# FPGA_Power_SPI.net
KiCad netlist of a schematic drawn in Altium Designer
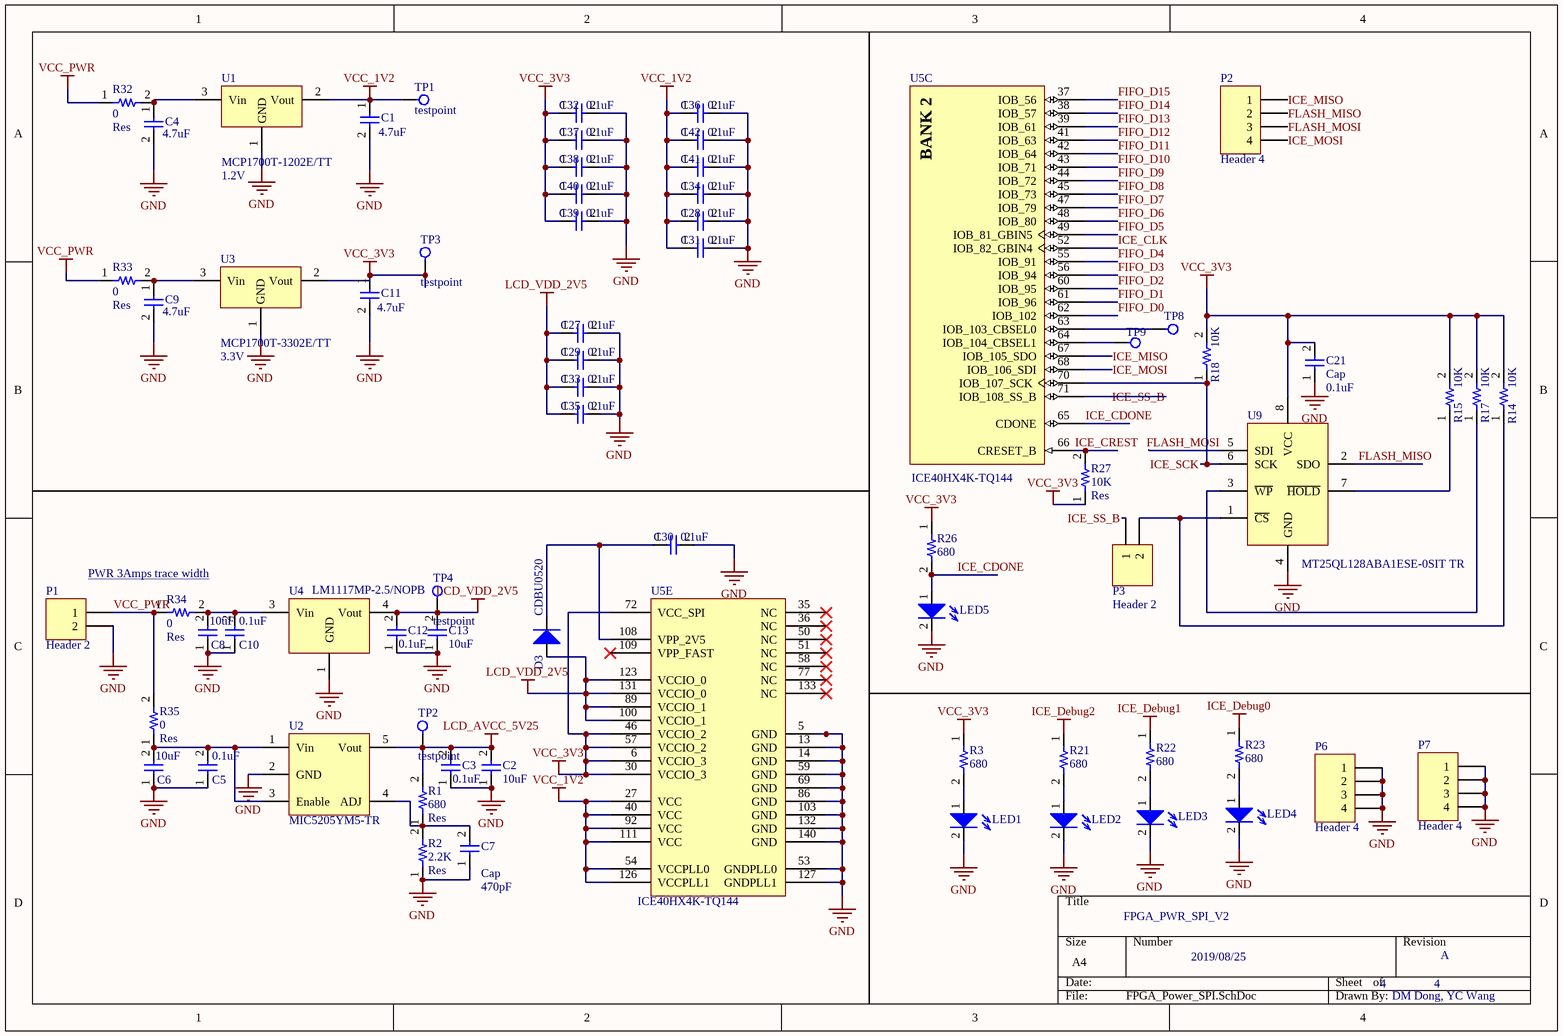
[diagram p0: FPGA_Power_SPI.SchDoc]

(export (version "E")
  (design (tool "Eeschema 10.0.6"))
  (components
    (comp (ref "C1")
      (value "4.7uF")
      (footprint "Cap_4.7uF")
      (description "Multilayer Ceramic Capacitors MLCC - SMD/SMT 6.3V 4.7uF 0603 X5R 10%")
      (fields (field (name "Comment") "C0603C475K9PAC7411") (field (name "CREATED BY") "Daoming Dong"))
      (libsource (lib "USB_FPGA_SLM_v1") (part "Cap_4.7uF"))
    )
    (comp (ref "C2")
      (value "10uF")
      (footprint "Cap_10uF")
      (description "Multilayer Ceramic Capacitors MLCC - SMD/SMT 0603 6.3V 10uF X5R 10% Soft Term")
      (fields (field (name "Comment") "C1608X5R0J106K080AE") (field (name "CREATED BY") "Daoming Dong"))
      (libsource (lib "USB_FPGA_SLM_v1") (part "Cap_10uF"))
    )
    (comp (ref "C3")
      (value "0.1uF")
      (footprint "Cap_0.1uF")
      (description "Multilayer Ceramic Capacitors MLCC - SMD/SMT 0.1uF 10% 50V AEC-Q200")
      (fields (field (name "Comment") "AC0603KRX7R9BB104") (field (name "CREATED BY") "Daoming Dong"))
      (libsource (lib "USB_FPGA_SLM_v1") (part "Cap_0.1uF"))
    )
    (comp (ref "C4")
      (value "4.7uF")
      (footprint "Cap_4.7uF")
      (description "Multilayer Ceramic Capacitors MLCC - SMD/SMT 6.3V 4.7uF 0603 X5R 10%")
      (fields (field (name "Comment") "C0603C475K9PAC7411") (field (name "CREATED BY") "Daoming Dong"))
      (libsource (lib "USB_FPGA_SLM_v1") (part "Cap_4.7uF"))
    )
    (comp (ref "C5")
      (value "0.1uF")
      (footprint "Cap_0.1uF")
      (description "Multilayer Ceramic Capacitors MLCC - SMD/SMT 0.1uF 10% 50V AEC-Q200")
      (fields (field (name "Comment") "AC0603KRX7R9BB104") (field (name "CREATED BY") "Daoming Dong"))
      (libsource (lib "USB_FPGA_SLM_v1") (part "Cap_0.1uF"))
    )
    (comp (ref "C6")
      (value "10uF")
      (footprint "Cap_10uF")
      (description "Multilayer Ceramic Capacitors MLCC - SMD/SMT 0603 6.3V 10uF X5R 10% Soft Term")
      (fields (field (name "Comment") "C1608X5R0J106K080AE") (field (name "CREATED BY") "Daoming Dong"))
      (libsource (lib "USB_FPGA_SLM_v1") (part "Cap_10uF"))
    )
    (comp (ref "C7")
      (value "470pF")
      (footprint "CAP_470pF")
      (description "Multilayer Ceramic Capacitors MLCC - SMD/SMT 25V 470pF X7R 0402 10% AEC-Q200")
      (fields
        (field (name "COMPONENT NAME") "Cap")
        (field (name "Comment") "C0402S471K3RACAUTO")
        (field (name "CREATED BY") "Daoming Dong")
      )
      (libsource (lib "USB_FPGA_SLM_v1") (part "Cap_470pF"))
    )
    (comp (ref "C8")
      (value "10uF")
      (footprint "Cap_10uF")
      (description "Multilayer Ceramic Capacitors MLCC - SMD/SMT 0603 6.3V 10uF X5R 10% Soft Term")
      (fields (field (name "Comment") "C1608X5R0J106K080AE") (field (name "CREATED BY") "Daoming Dong"))
      (libsource (lib "USB_FPGA_SLM_v1") (part "Cap_10uF"))
    )
    (comp (ref "C9")
      (value "4.7uF")
      (footprint "Cap_4.7uF")
      (description "Multilayer Ceramic Capacitors MLCC - SMD/SMT 6.3V 4.7uF 0603 X5R 10%")
      (fields (field (name "Comment") "C0603C475K9PAC7411") (field (name "CREATED BY") "Daoming Dong"))
      (libsource (lib "USB_FPGA_SLM_v1") (part "Cap_4.7uF"))
    )
    (comp (ref "C10")
      (value "0.1uF")
      (footprint "Cap_0.1uF")
      (description "Multilayer Ceramic Capacitors MLCC - SMD/SMT 0.1uF 10% 50V AEC-Q200")
      (fields (field (name "Comment") "AC0603KRX7R9BB104") (field (name "CREATED BY") "Daoming Dong"))
      (libsource (lib "USB_FPGA_SLM_v1") (part "Cap_0.1uF"))
    )
    (comp (ref "C11")
      (value "4.7uF")
      (footprint "Cap_4.7uF")
      (description "Multilayer Ceramic Capacitors MLCC - SMD/SMT 6.3V 4.7uF 0603 X5R 10%")
      (fields (field (name "Comment") "C0603C475K9PAC7411") (field (name "CREATED BY") "Daoming Dong"))
      (libsource (lib "USB_FPGA_SLM_v1") (part "Cap_4.7uF"))
    )
    (comp (ref "C12")
      (value "0.1uF")
      (footprint "Cap_0.1uF")
      (description "Multilayer Ceramic Capacitors MLCC - SMD/SMT 0.1uF 10% 50V AEC-Q200")
      (fields (field (name "Comment") "AC0603KRX7R9BB104") (field (name "CREATED BY") "Daoming Dong"))
      (libsource (lib "USB_FPGA_SLM_v1") (part "Cap_0.1uF"))
    )
    (comp (ref "C13")
      (value "10uF")
      (footprint "Cap_10uF")
      (description "Multilayer Ceramic Capacitors MLCC - SMD/SMT 0603 6.3V 10uF X5R 10% Soft Term")
      (fields (field (name "Comment") "C1608X5R0J106K080AE") (field (name "CREATED BY") "Daoming Dong"))
      (libsource (lib "USB_FPGA_SLM_v1") (part "Cap_10uF"))
    )
    (comp (ref "C21")
      (value "0.1uF")
      (footprint "Cap_0.1uF")
      (description "Multilayer Ceramic Capacitors MLCC - SMD/SMT 0.1uF 10% 50V AEC-Q200")
      (fields
        (field (name "COMPONENT NAME") "Cap")
        (field (name "Comment") "AC0603KRX7R9BB104")
        (field (name "CREATED BY") "Daoming Dong")
      )
      (libsource (lib "USB_FPGA_SLM_v1") (part "Cap_0.1uF"))
    )
    (comp (ref "C27")
      (value "0.1uF")
      (footprint "Cap_0.1uF")
      (description "Multilayer Ceramic Capacitors MLCC - SMD/SMT 0.1uF 10% 50V AEC-Q200")
      (fields (field (name "Comment") "AC0603KRX7R9BB104") (field (name "CREATED BY") "Daoming Dong"))
      (libsource (lib "USB_FPGA_SLM_v1") (part "Cap_0.1uF"))
    )
    (comp (ref "C28")
      (value "0.1uF")
      (footprint "Cap_0.1uF")
      (description "Multilayer Ceramic Capacitors MLCC - SMD/SMT 0.1uF 10% 50V AEC-Q200")
      (fields (field (name "Comment") "AC0603KRX7R9BB104") (field (name "CREATED BY") "Daoming Dong"))
      (libsource (lib "USB_FPGA_SLM_v1") (part "Cap_0.1uF"))
    )
    (comp (ref "C29")
      (value "0.1uF")
      (footprint "Cap_0.1uF")
      (description "Multilayer Ceramic Capacitors MLCC - SMD/SMT 0.1uF 10% 50V AEC-Q200")
      (fields (field (name "Comment") "AC0603KRX7R9BB104") (field (name "CREATED BY") "Daoming Dong"))
      (libsource (lib "USB_FPGA_SLM_v1") (part "Cap_0.1uF"))
    )
    (comp (ref "C30")
      (value "0.1uF")
      (footprint "Cap_0.1uF")
      (description "Multilayer Ceramic Capacitors MLCC - SMD/SMT 0.1uF 10% 50V AEC-Q200")
      (fields (field (name "Comment") "AC0603KRX7R9BB104") (field (name "CREATED BY") "Daoming Dong"))
      (libsource (lib "USB_FPGA_SLM_v1") (part "Cap_0.1uF"))
    )
    (comp (ref "C31")
      (value "0.1uF")
      (footprint "Cap_0.1uF")
      (description "Multilayer Ceramic Capacitors MLCC - SMD/SMT 0.1uF 10% 50V AEC-Q200")
      (fields (field (name "Comment") "AC0603KRX7R9BB104") (field (name "CREATED BY") "Daoming Dong"))
      (libsource (lib "USB_FPGA_SLM_v1") (part "Cap_0.1uF"))
    )
    (comp (ref "C32")
      (value "0.1uF")
      (footprint "Cap_0.1uF")
      (description "Multilayer Ceramic Capacitors MLCC - SMD/SMT 0.1uF 10% 50V AEC-Q200")
      (fields (field (name "Comment") "AC0603KRX7R9BB104") (field (name "CREATED BY") "Daoming Dong"))
      (libsource (lib "USB_FPGA_SLM_v1") (part "Cap_0.1uF"))
    )
    (comp (ref "C33")
      (value "0.1uF")
      (footprint "Cap_0.1uF")
      (description "Multilayer Ceramic Capacitors MLCC - SMD/SMT 0.1uF 10% 50V AEC-Q200")
      (fields (field (name "Comment") "AC0603KRX7R9BB104") (field (name "CREATED BY") "Daoming Dong"))
      (libsource (lib "USB_FPGA_SLM_v1") (part "Cap_0.1uF"))
    )
    (comp (ref "C34")
      (value "0.1uF")
      (footprint "Cap_0.1uF")
      (description "Multilayer Ceramic Capacitors MLCC - SMD/SMT 0.1uF 10% 50V AEC-Q200")
      (fields (field (name "Comment") "AC0603KRX7R9BB104") (field (name "CREATED BY") "Daoming Dong"))
      (libsource (lib "USB_FPGA_SLM_v1") (part "Cap_0.1uF"))
    )
    (comp (ref "C35")
      (value "0.1uF")
      (footprint "Cap_0.1uF")
      (description "Multilayer Ceramic Capacitors MLCC - SMD/SMT 0.1uF 10% 50V AEC-Q200")
      (fields (field (name "Comment") "AC0603KRX7R9BB104") (field (name "CREATED BY") "Daoming Dong"))
      (libsource (lib "USB_FPGA_SLM_v1") (part "Cap_0.1uF"))
    )
    (comp (ref "C36")
      (value "0.1uF")
      (footprint "Cap_0.1uF")
      (description "Multilayer Ceramic Capacitors MLCC - SMD/SMT 0.1uF 10% 50V AEC-Q200")
      (fields (field (name "Comment") "AC0603KRX7R9BB104") (field (name "CREATED BY") "Daoming Dong"))
      (libsource (lib "USB_FPGA_SLM_v1") (part "Cap_0.1uF"))
    )
    (comp (ref "C37")
      (value "0.1uF")
      (footprint "Cap_0.1uF")
      (description "Multilayer Ceramic Capacitors MLCC - SMD/SMT 0.1uF 10% 50V AEC-Q200")
      (fields (field (name "Comment") "AC0603KRX7R9BB104") (field (name "CREATED BY") "Daoming Dong"))
      (libsource (lib "USB_FPGA_SLM_v1") (part "Cap_0.1uF"))
    )
    (comp (ref "C38")
      (value "0.1uF")
      (footprint "Cap_0.1uF")
      (description "Multilayer Ceramic Capacitors MLCC - SMD/SMT 0.1uF 10% 50V AEC-Q200")
      (fields (field (name "Comment") "AC0603KRX7R9BB104") (field (name "CREATED BY") "Daoming Dong"))
      (libsource (lib "USB_FPGA_SLM_v1") (part "Cap_0.1uF"))
    )
    (comp (ref "C39")
      (value "0.1uF")
      (footprint "Cap_0.1uF")
      (description "Multilayer Ceramic Capacitors MLCC - SMD/SMT 0.1uF 10% 50V AEC-Q200")
      (fields (field (name "Comment") "AC0603KRX7R9BB104") (field (name "CREATED BY") "Daoming Dong"))
      (libsource (lib "USB_FPGA_SLM_v1") (part "Cap_0.1uF"))
    )
    (comp (ref "C40")
      (value "0.1uF")
      (footprint "Cap_0.1uF")
      (description "Multilayer Ceramic Capacitors MLCC - SMD/SMT 0.1uF 10% 50V AEC-Q200")
      (fields (field (name "Comment") "AC0603KRX7R9BB104") (field (name "CREATED BY") "Daoming Dong"))
      (libsource (lib "USB_FPGA_SLM_v1") (part "Cap_0.1uF"))
    )
    (comp (ref "C41")
      (value "0.1uF")
      (footprint "Cap_0.1uF")
      (description "Multilayer Ceramic Capacitors MLCC - SMD/SMT 0.1uF 10% 50V AEC-Q200")
      (fields (field (name "Comment") "AC0603KRX7R9BB104") (field (name "CREATED BY") "Daoming Dong"))
      (libsource (lib "USB_FPGA_SLM_v1") (part "Cap_0.1uF"))
    )
    (comp (ref "C42")
      (value "0.1uF")
      (footprint "Cap_0.1uF")
      (description "Multilayer Ceramic Capacitors MLCC - SMD/SMT 0.1uF 10% 50V AEC-Q200")
      (fields (field (name "Comment") "AC0603KRX7R9BB104") (field (name "CREATED BY") "Daoming Dong"))
      (libsource (lib "USB_FPGA_SLM_v1") (part "Cap_0.1uF"))
    )
    (comp (ref "D3")
      (value "CDBU0520")
      (footprint "SchottkyDiode_CDBU0520")
      (description "Schottky Diodes & Rectifiers VR=20V, IO=500mA")
      (fields (field (name "CREATED BY") "Daoming Dong"))
      (libsource (lib "USB_FPGA_SLM_v1") (part "SDiode_CDBU0520"))
    )
    (comp (ref "LED1")
      (value "TLMS1000-GS08")
      (footprint "LED_RED")
      (description "Standard LEDs - SMD RED")
      (fields (field (name "CREATED BY") "Daoming Dong"))
      (libsource (lib "USB_FPGA_SLM_v1") (part "LED_RED"))
    )
    (comp (ref "LED2")
      (value "TLMS1000-GS08")
      (footprint "LED_RED")
      (description "Standard LEDs - SMD RED")
      (fields (field (name "CREATED BY") "Daoming Dong"))
      (libsource (lib "USB_FPGA_SLM_v1") (part "LED_RED"))
    )
    (comp (ref "LED3")
      (value "TLMS1000-GS08")
      (footprint "LED_RED")
      (description "Standard LEDs - SMD RED")
      (fields (field (name "CREATED BY") "Daoming Dong"))
      (libsource (lib "USB_FPGA_SLM_v1") (part "LED_RED"))
    )
    (comp (ref "LED4")
      (value "TLMS1000-GS08")
      (footprint "LED_RED")
      (description "Standard LEDs - SMD RED")
      (fields (field (name "CREATED BY") "Daoming Dong"))
      (libsource (lib "USB_FPGA_SLM_v1") (part "LED_RED"))
    )
    (comp (ref "LED5")
      (value "TLMS1000-GS08")
      (footprint "LED_RED")
      (description "Standard LEDs - SMD RED")
      (fields (field (name "CREATED BY") "Daoming Dong"))
      (libsource (lib "USB_FPGA_SLM_v1") (part "LED_RED"))
    )
    (comp (ref "P1")
      (value "Header 2")
      (footprint "HDR1X2")
      (description "Header, 2-Pin")
      (fields (field (name "PUBLISHER") "Altium Limited"))
      (libsource (lib "") (part "Header 2_1"))
    )
    (comp (ref "P2")
      (value "Header 4")
      (footprint "HDR2X2")
      (description "Header, 4-Pin")
      (fields (field (name "PUBLISHER") "Altium Limited"))
      (libsource (lib "Miscellaneous Connectors") (part "Header 4"))
    )
    (comp (ref "P3")
      (value "Header 2")
      (footprint "HDR1X2")
      (description "Header, 2-Pin")
      (fields (field (name "PUBLISHER") "Altium Limited"))
      (libsource (lib "Miscellaneous Connectors") (part "Header 2"))
    )
    (comp (ref "P6")
      (value "Header 4")
      (footprint "HDR2X2")
      (description "Header, 4-Pin")
      (fields (field (name "PUBLISHER") "Altium Limited"))
      (libsource (lib "Miscellaneous Connectors") (part "Header 4"))
    )
    (comp (ref "P7")
      (value "Header 4")
      (footprint "HDR2X2")
      (description "Header, 4-Pin")
      (fields (field (name "PUBLISHER") "Altium Limited"))
      (libsource (lib "Miscellaneous Connectors") (part "Header 4"))
    )
    (comp (ref "R1")
      (value "680")
      (footprint "RES_680")
      (description "Thin Film Resistors - SMD 680 ohm 1% 50 ppm Thin Film")
      (fields
        (field (name "COMPONENT NAME") "Res")
        (field (name "Comment") "RT0603FRE13680RL")
        (field (name "CREATED BY") "Daoming Dong")
      )
      (libsource (lib "USB_FPGA_SLM_v1") (part "Res_680"))
    )
    (comp (ref "R2")
      (value "2.2K")
      (footprint "RES_2.2K")
      (description "Thick Film Resistors - SMD 1/10Watt 2.2Kohms 5% Commercial Use")
      (fields
        (field (name "COMPONENT NAME") "Res")
        (field (name "Comment") "CRCW06032K20JNEAC")
        (field (name "CREATED BY") "Daoming Dong")
      )
      (libsource (lib "USB_FPGA_SLM_v1") (part "Res_2.2K"))
    )
    (comp (ref "R3")
      (value "680")
      (footprint "RES_680")
      (description "Thin Film Resistors - SMD 680 ohm 1% 50 ppm Thin Film")
      (fields (field (name "Comment") "RT0603FRE13680RL") (field (name "CREATED BY") "Daoming Dong"))
      (libsource (lib "USB_FPGA_SLM_v1") (part "Res_680"))
    )
    (comp (ref "R14")
      (value "10K")
      (footprint "RES_10K")
      (description "Thin Film Resistors - SMD 10K ohm 0.05% 50 ppm High-Precision")
      (fields (field (name "Comment") "RT0603WRE0710KL") (field (name "CREATED BY") "Daoming Dong"))
      (libsource (lib "USB_FPGA_SLM_v1") (part "Res_10K"))
    )
    (comp (ref "R15")
      (value "10K")
      (footprint "RES_10K")
      (description "Thin Film Resistors - SMD 10K ohm 0.05% 50 ppm High-Precision")
      (fields (field (name "Comment") "RT0603WRE0710KL") (field (name "CREATED BY") "Daoming Dong"))
      (libsource (lib "USB_FPGA_SLM_v1") (part "Res_10K"))
    )
    (comp (ref "R17")
      (value "10K")
      (footprint "RES_10K")
      (description "Thin Film Resistors - SMD 10K ohm 0.05% 50 ppm High-Precision")
      (fields (field (name "Comment") "RT0603WRE0710KL") (field (name "CREATED BY") "Daoming Dong"))
      (libsource (lib "USB_FPGA_SLM_v1") (part "Res_10K"))
    )
    (comp (ref "R18")
      (value "10K")
      (footprint "RES_10K")
      (description "Thin Film Resistors - SMD 10K ohm 0.05% 50 ppm High-Precision")
      (fields (field (name "Comment") "RT0603WRE0710KL") (field (name "CREATED BY") "Daoming Dong"))
      (libsource (lib "USB_FPGA_SLM_v1") (part "Res_10K"))
    )
    (comp (ref "R21")
      (value "680")
      (footprint "RES_680")
      (description "Thin Film Resistors - SMD 680 ohm 1% 50 ppm Thin Film")
      (fields (field (name "Comment") "RT0603FRE13680RL") (field (name "CREATED BY") "Daoming Dong"))
      (libsource (lib "USB_FPGA_SLM_v1") (part "Res_680"))
    )
    (comp (ref "R22")
      (value "680")
      (footprint "RES_680")
      (description "Thin Film Resistors - SMD 680 ohm 1% 50 ppm Thin Film")
      (fields (field (name "Comment") "RT0603FRE13680RL") (field (name "CREATED BY") "Daoming Dong"))
      (libsource (lib "USB_FPGA_SLM_v1") (part "Res_680"))
    )
    (comp (ref "R23")
      (value "680")
      (footprint "RES_680")
      (description "Thin Film Resistors - SMD 680 ohm 1% 50 ppm Thin Film")
      (fields (field (name "Comment") "RT0603FRE13680RL") (field (name "CREATED BY") "Daoming Dong"))
      (libsource (lib "USB_FPGA_SLM_v1") (part "Res_680"))
    )
    (comp (ref "R26")
      (value "680")
      (footprint "RES_680")
      (description "Thin Film Resistors - SMD 680 ohm 1% 50 ppm Thin Film")
      (fields (field (name "Comment") "RT0603FRE13680RL") (field (name "CREATED BY") "Daoming Dong"))
      (libsource (lib "USB_FPGA_SLM_v1") (part "Res_680"))
    )
    (comp (ref "R27")
      (value "10K")
      (footprint "RES_10K")
      (description "Thin Film Resistors - SMD 10K ohm 0.05% 50 ppm High-Precision")
      (fields
        (field (name "COMPONENT NAME") "Res")
        (field (name "Comment") "RT0603WRE0710KL")
        (field (name "CREATED BY") "Daoming Dong")
      )
      (libsource (lib "USB_FPGA_SLM_v1") (part "Res_10K"))
    )
    (comp (ref "R32")
      (value "0")
      (footprint "RES_0")
      (description "Thick Film Resistors - SMD 1/10Watt 0ohms Commercial Use")
      (fields
        (field (name "COMPONENT NAME") "Res")
        (field (name "Comment") "CRCW06030000Z0EAC")
        (field (name "CREATED BY") "Daoming Dong")
      )
      (libsource (lib "USB_FPGA_SLM_v1") (part "Res_0"))
    )
    (comp (ref "R33")
      (value "0")
      (footprint "RES_0")
      (description "Thick Film Resistors - SMD 1/10Watt 0ohms Commercial Use")
      (fields
        (field (name "COMPONENT NAME") "Res")
        (field (name "Comment") "CRCW06030000Z0EAC")
        (field (name "CREATED BY") "Daoming Dong")
      )
      (libsource (lib "USB_FPGA_SLM_v1") (part "Res_0"))
    )
    (comp (ref "R34")
      (value "0")
      (footprint "RES_0")
      (description "Thick Film Resistors - SMD 1/10Watt 0ohms Commercial Use")
      (fields
        (field (name "COMPONENT NAME") "Res")
        (field (name "Comment") "CRCW06030000Z0EAC")
        (field (name "CREATED BY") "Daoming Dong")
      )
      (libsource (lib "USB_FPGA_SLM_v1") (part "Res_0"))
    )
    (comp (ref "R35")
      (value "0")
      (footprint "RES_0")
      (description "Thick Film Resistors - SMD 1/10Watt 0ohms Commercial Use")
      (fields
        (field (name "COMPONENT NAME") "Res")
        (field (name "Comment") "CRCW06030000Z0EAC")
        (field (name "CREATED BY") "Daoming Dong")
      )
      (libsource (lib "USB_FPGA_SLM_v1") (part "Res_0"))
    )
    (comp (ref "TP1")
      (value "testpoint")
      (footprint "testpoint")
      (description "Testpoint for testing voltage")
      (fields (field (name "CREATED BY") "Daoming Dong"))
      (libsource (lib "USB_FPGA_SLM_v1") (part "Testpoint"))
    )
    (comp (ref "TP2")
      (value "testpoint")
      (footprint "testpoint")
      (description "Testpoint for testing voltage")
      (fields (field (name "CREATED BY") "Daoming Dong"))
      (libsource (lib "USB_FPGA_SLM_v1") (part "Testpoint"))
    )
    (comp (ref "TP3")
      (value "testpoint")
      (footprint "testpoint")
      (description "Testpoint for testing voltage")
      (fields (field (name "CREATED BY") "Daoming Dong"))
      (libsource (lib "USB_FPGA_SLM_v1") (part "Testpoint"))
    )
    (comp (ref "TP4")
      (value "testpoint")
      (footprint "testpoint")
      (description "Testpoint for testing voltage")
      (fields (field (name "CREATED BY") "Daoming Dong"))
      (libsource (lib "USB_FPGA_SLM_v1") (part "Testpoint"))
    )
    (comp (ref "TP8")
      (value "Testpoint")
      (footprint "testpoint")
      (description "Testpoint for testing voltage")
      (fields (field (name "CREATED BY") "Daoming Dong"))
      (libsource (lib "USB_FPGA_SLM_v1") (part "Testpoint"))
    )
    (comp (ref "TP9")
      (value "Testpoint")
      (footprint "testpoint")
      (description "Testpoint for testing voltage")
      (fields (field (name "CREATED BY") "Daoming Dong"))
      (libsource (lib "USB_FPGA_SLM_v1") (part "Testpoint"))
    )
    (comp (ref "U1")
      (value "MCP1700T-1202E/TT")
      (footprint "MIC_LDO_1V2")
      (description "LDO Voltage Regulators 250mA Adj LDO 2%")
      (fields (field (name "ALTIUM_VALUE") "1.2V") (field (name "CREATED BY") "Daoming Dong"))
      (libsource (lib "USB_FPGA_SLM_v1") (part "MIC_LDO_1V2"))
    )
    (comp (ref "U2")
      (value "MIC5205YM5-TR")
      (footprint "MIC5205YM5")
      (description "LDO Voltage Regulators 150mA 1% Low Noise LDO")
      (fields (field (name "CREATED BY") "Daoming Dong"))
      (libsource (lib "USB_FPGA_SLM_v1") (part "MIC5205YM5"))
    )
    (comp (ref "U3")
      (value "MCP1700T-3302E/TT")
      (footprint "MIC_LDO_3V3")
      (description "3.3v LDO Voltage Regulators 250mA Adj LDO 2%")
      (fields (field (name "ALTIUM_VALUE") "3.3V") (field (name "CREATED BY") "Daoming Dong"))
      (libsource (lib "USB_FPGA_SLM_v1") (part "MIC_LDO_3V3"))
    )
    (comp (ref "U4")
      (value "LM1117MP-2.5/NOPB")
      (footprint "LM1117MP-2.5/NOPB")
      (description "LDO Voltage Regulators 800mA LDO Linear Reg")
      (fields (field (name "CREATED BY") "Daoming Dong"))
      (libsource (lib "USB_FPGA_SLM_v1") (part "LDO_2V5"))
    )
    (comp (ref "U5")
      (value "ICE40HX4K-TQ144")
      (footprint "LATC-TQFP-144_L")
      (fields (field (name "MANUFACTURER") "Lattice Semiconductor"))
      (libsource (lib "Lattice iCE40") (part "ICE40HX4K-TQ144"))
    )
    (comp (ref "U9")
      (value "MT25QL128ABA1ESE-0SIT TR")
      (footprint "Flash")
      (description "NOR Flash SPI FLASH NOR SLC 32MX4 SOIC")
      (fields (field (name "CREATED BY") "Daoming Dong"))
      (libsource (lib "USB_FPGA_SLM_v1") (part "Flash"))
    )
  )
  (nets
    (net (code "1") (name "/FIFO_D0") (class "Default")
      (node (ref "U5") (pin "62") (pinfunction "IOB_102_62") (pintype "bidirectional"))
    )
    (net (code "2") (name "/FIFO_D1") (class "Default")
      (node (ref "U5") (pin "61") (pinfunction "IOB_96_61") (pintype "bidirectional"))
    )
    (net (code "3") (name "/FIFO_D2") (class "Default")
      (node (ref "U5") (pin "60") (pinfunction "IOB_95_60") (pintype "bidirectional"))
    )
    (net (code "4") (name "/FIFO_D3") (class "Default")
      (node (ref "U5") (pin "56") (pinfunction "IOB_94_56") (pintype "bidirectional"))
    )
    (net (code "5") (name "/FIFO_D4") (class "Default")
      (node (ref "U5") (pin "55") (pinfunction "IOB_91_55") (pintype "bidirectional"))
    )
    (net (code "6") (name "/FIFO_D5") (class "Default")
      (node (ref "U5") (pin "49") (pinfunction "IOB_81_GBIN5_49") (pintype "bidirectional"))
    )
    (net (code "7") (name "/FIFO_D6") (class "Default")
      (node (ref "U5") (pin "48") (pinfunction "IOB_80_48") (pintype "bidirectional"))
    )
    (net (code "8") (name "/FIFO_D7") (class "Default")
      (node (ref "U5") (pin "47") (pinfunction "IOB_79_47") (pintype "bidirectional"))
    )
    (net (code "9") (name "/FIFO_D8") (class "Default")
      (node (ref "U5") (pin "45") (pinfunction "IOB_73_45") (pintype "bidirectional"))
    )
    (net (code "10") (name "/FIFO_D9") (class "Default")
      (node (ref "U5") (pin "44") (pinfunction "IOB_72_44") (pintype "bidirectional"))
    )
    (net (code "11") (name "/FIFO_D10") (class "Default")
      (node (ref "U5") (pin "43") (pinfunction "IOB_71_43") (pintype "bidirectional"))
    )
    (net (code "12") (name "/FIFO_D11") (class "Default")
      (node (ref "U5") (pin "42") (pinfunction "IOB_64_42") (pintype "bidirectional"))
    )
    (net (code "13") (name "/FIFO_D12") (class "Default")
      (node (ref "U5") (pin "41") (pinfunction "IOB_63_41") (pintype "bidirectional"))
    )
    (net (code "14") (name "/FIFO_D13") (class "Default")
      (node (ref "U5") (pin "39") (pinfunction "IOB_61_39") (pintype "bidirectional"))
    )
    (net (code "15") (name "/FIFO_D14") (class "Default")
      (node (ref "U5") (pin "38") (pinfunction "IOB_57_38") (pintype "bidirectional"))
    )
    (net (code "16") (name "/FIFO_D15") (class "Default")
      (node (ref "U5") (pin "37") (pinfunction "IOB_56_37") (pintype "bidirectional"))
    )
    (net (code "17") (name "/FLASH_MISO") (class "Default")
      (node (ref "P2") (pin "2") (pinfunction "2_2") (pintype "passive"))
      (node (ref "U9") (pin "2") (pinfunction "SDO_2") (pintype "passive"))
    )
    (net (code "18") (name "/FLASH_MOSI") (class "Default")
      (node (ref "P2") (pin "3") (pinfunction "3_3") (pintype "passive"))
      (node (ref "U9") (pin "5") (pinfunction "SDI_5") (pintype "passive"))
    )
    (net (code "19") (name "/ICE_CDONE") (class "Default")
      (node (ref "LED5") (pin "1") (pinfunction "Anode_1") (pintype "passive"))
      (node (ref "R26") (pin "2") (pinfunction "2_2") (pintype "passive"))
      (node (ref "U5") (pin "65") (pinfunction "CDONE_65") (pintype "bidirectional"))
    )
    (net (code "20") (name "/ICE_CLK") (class "Default")
      (node (ref "U5") (pin "52") (pinfunction "IOB_82_GBIN4_52") (pintype "bidirectional"))
    )
    (net (code "21") (name "/ICE_CREST") (class "Default")
      (node (ref "R27") (pin "2") (pinfunction "2_2") (pintype "passive"))
      (node (ref "U5") (pin "66") (pinfunction "CRESET_B_66") (pintype "input"))
    )
    (net (code "22") (name "/ICE_MISO") (class "Default")
      (node (ref "P2") (pin "1") (pinfunction "1_1") (pintype "passive"))
      (node (ref "U5") (pin "67") (pinfunction "IOB_105_SDO_67") (pintype "bidirectional"))
    )
    (net (code "23") (name "/ICE_MOSI") (class "Default")
      (node (ref "P2") (pin "4") (pinfunction "4_4") (pintype "passive"))
      (node (ref "U5") (pin "68") (pinfunction "IOB_106_SDI_68") (pintype "bidirectional"))
    )
    (net (code "24") (name "/ICE_SCK") (class "Default")
      (node (ref "R18") (pin "1") (pinfunction "1_1") (pintype "passive"))
      (node (ref "U5") (pin "70") (pinfunction "IOB_107_SCK_70") (pintype "bidirectional"))
      (node (ref "U9") (pin "6") (pinfunction "SCK_6") (pintype "passive"))
    )
    (net (code "25") (name "/ICE_SS_B") (class "Default")
      (node (ref "P3") (pin "1") (pinfunction "1_1") (pintype "passive"))
      (node (ref "U5") (pin "71") (pinfunction "IOB_108_SS_B_71") (pintype "bidirectional"))
    )
    (net (code "26") (name "GND") (class "Default")
      (node (ref "C1") (pin "2") (pinfunction "2_2") (pintype "passive"))
      (node (ref "C10") (pin "1") (pinfunction "1_1") (pintype "passive"))
      (node (ref "C11") (pin "2") (pinfunction "2_2") (pintype "passive"))
      (node (ref "C12") (pin "1") (pinfunction "1_1") (pintype "passive"))
      (node (ref "C13") (pin "1") (pinfunction "1_1") (pintype "passive"))
      (node (ref "C2") (pin "1") (pinfunction "1_1") (pintype "passive"))
      (node (ref "C21") (pin "1") (pinfunction "1_1") (pintype "passive"))
      (node (ref "C27") (pin "2") (pinfunction "2_2") (pintype "passive"))
      (node (ref "C28") (pin "2") (pinfunction "2_2") (pintype "passive"))
      (node (ref "C29") (pin "2") (pinfunction "2_2") (pintype "passive"))
      (node (ref "C3") (pin "1") (pinfunction "1_1") (pintype "passive"))
      (node (ref "C30") (pin "2") (pinfunction "2_2") (pintype "passive"))
      (node (ref "C31") (pin "2") (pinfunction "2_2") (pintype "passive"))
      (node (ref "C32") (pin "2") (pinfunction "2_2") (pintype "passive"))
      (node (ref "C33") (pin "2") (pinfunction "2_2") (pintype "passive"))
      (node (ref "C34") (pin "2") (pinfunction "2_2") (pintype "passive"))
      (node (ref "C35") (pin "2") (pinfunction "2_2") (pintype "passive"))
      (node (ref "C36") (pin "2") (pinfunction "2_2") (pintype "passive"))
      (node (ref "C37") (pin "2") (pinfunction "2_2") (pintype "passive"))
      (node (ref "C38") (pin "2") (pinfunction "2_2") (pintype "passive"))
      (node (ref "C39") (pin "2") (pinfunction "2_2") (pintype "passive"))
      (node (ref "C4") (pin "2") (pinfunction "2_2") (pintype "passive"))
      (node (ref "C40") (pin "2") (pinfunction "2_2") (pintype "passive"))
      (node (ref "C41") (pin "2") (pinfunction "2_2") (pintype "passive"))
      (node (ref "C42") (pin "2") (pinfunction "2_2") (pintype "passive"))
      (node (ref "C5") (pin "1") (pinfunction "1_1") (pintype "passive"))
      (node (ref "C6") (pin "1") (pinfunction "1_1") (pintype "passive"))
      (node (ref "C7") (pin "1") (pinfunction "1_1") (pintype "passive"))
      (node (ref "C8") (pin "1") (pinfunction "1_1") (pintype "passive"))
      (node (ref "C9") (pin "2") (pinfunction "2_2") (pintype "passive"))
      (node (ref "LED1") (pin "2") (pinfunction "Cathode_2") (pintype "passive"))
      (node (ref "LED2") (pin "2") (pinfunction "Cathode_2") (pintype "passive"))
      (node (ref "LED3") (pin "2") (pinfunction "Cathode_2") (pintype "passive"))
      (node (ref "LED4") (pin "2") (pinfunction "Cathode_2") (pintype "passive"))
      (node (ref "LED5") (pin "2") (pinfunction "Cathode_2") (pintype "passive"))
      (node (ref "P1") (pin "2") (pinfunction "2_2") (pintype "passive"))
      (node (ref "P6") (pin "1") (pinfunction "1_1") (pintype "passive"))
      (node (ref "P6") (pin "2") (pinfunction "2_2") (pintype "passive"))
      (node (ref "P6") (pin "3") (pinfunction "3_3") (pintype "passive"))
      (node (ref "P6") (pin "4") (pinfunction "4_4") (pintype "passive"))
      (node (ref "P7") (pin "1") (pinfunction "1_1") (pintype "passive"))
      (node (ref "P7") (pin "2") (pinfunction "2_2") (pintype "passive"))
      (node (ref "P7") (pin "3") (pinfunction "3_3") (pintype "passive"))
      (node (ref "P7") (pin "4") (pinfunction "4_4") (pintype "passive"))
      (node (ref "R2") (pin "1") (pinfunction "1_1") (pintype "passive"))
      (node (ref "U1") (pin "1") (pinfunction "GND_1") (pintype "passive"))
      (node (ref "U2") (pin "2") (pinfunction "GND_2") (pintype "passive"))
      (node (ref "U3") (pin "1") (pinfunction "GND_1") (pintype "passive"))
      (node (ref "U4") (pin "1") (pinfunction "GND_1") (pintype "passive"))
      (node (ref "U5") (pin "103") (pinfunction "GND_103") (pintype "power_in"))
      (node (ref "U5") (pin "127") (pinfunction "GNDPLL1_127") (pintype "power_in"))
      (node (ref "U5") (pin "13") (pinfunction "GND_13") (pintype "power_in"))
      (node (ref "U5") (pin "132") (pinfunction "GND_132") (pintype "power_in"))
      (node (ref "U5") (pin "14") (pinfunction "GND_14") (pintype "power_in"))
      (node (ref "U5") (pin "140") (pinfunction "GND_140") (pintype "power_in"))
      (node (ref "U5") (pin "5") (pinfunction "GND_5") (pintype "power_in"))
      (node (ref "U5") (pin "53") (pinfunction "GNDPLL0_53") (pintype "power_in"))
      (node (ref "U5") (pin "59") (pinfunction "GND_59") (pintype "power_in"))
      (node (ref "U5") (pin "69") (pinfunction "GND_69") (pintype "power_in"))
      (node (ref "U5") (pin "86") (pinfunction "GND_86") (pintype "power_in"))
      (node (ref "U9") (pin "4") (pinfunction "GND_4") (pintype "passive"))
    )
    (net (code "27") (name "ICE_Debug0") (class "Default")
      (node (ref "R23") (pin "1") (pinfunction "1_1") (pintype "passive"))
    )
    (net (code "28") (name "ICE_Debug1") (class "Default")
      (node (ref "R22") (pin "1") (pinfunction "1_1") (pintype "passive"))
    )
    (net (code "29") (name "ICE_Debug2") (class "Default")
      (node (ref "R21") (pin "1") (pinfunction "1_1") (pintype "passive"))
    )
    (net (code "30") (name "LCD_AVCC_5V25") (class "Default")
      (node (ref "C2") (pin "2") (pinfunction "2_2") (pintype "passive"))
      (node (ref "C3") (pin "2") (pinfunction "2_2") (pintype "passive"))
      (node (ref "R1") (pin "2") (pinfunction "2_2") (pintype "passive"))
      (node (ref "TP2") (pin "1") (pinfunction "1_1") (pintype "passive"))
      (node (ref "U2") (pin "5") (pinfunction "Vout_5") (pintype "passive"))
    )
    (net (code "31") (name "LCD_VDD_2V5") (class "Default")
      (node (ref "C12") (pin "2") (pinfunction "2_2") (pintype "passive"))
      (node (ref "C13") (pin "2") (pinfunction "2_2") (pintype "passive"))
      (node (ref "C27") (pin "1") (pinfunction "1_1") (pintype "passive"))
      (node (ref "C29") (pin "1") (pinfunction "1_1") (pintype "passive"))
      (node (ref "C33") (pin "1") (pinfunction "1_1") (pintype "passive"))
      (node (ref "C35") (pin "1") (pinfunction "1_1") (pintype "passive"))
      (node (ref "D3") (pin "1") (pinfunction "Anode_1") (pintype "passive"))
      (node (ref "TP4") (pin "1") (pinfunction "1_1") (pintype "passive"))
      (node (ref "U4") (pin "4") (pinfunction "Vout_4") (pintype "power_in"))
      (node (ref "U5") (pin "100") (pinfunction "VCCIO_1_100") (pintype "power_in"))
      (node (ref "U5") (pin "123") (pinfunction "VCCIO_0_123") (pintype "power_in"))
      (node (ref "U5") (pin "131") (pinfunction "VCCIO_0_131") (pintype "power_in"))
      (node (ref "U5") (pin "89") (pinfunction "VCCIO_1_89") (pintype "power_in"))
    )
    (net (code "32") (name "Net-(D3-Cathode)") (class "Default")
      (node (ref "C30") (pin "1") (pinfunction "1_1") (pintype "passive"))
      (node (ref "D3") (pin "2") (pinfunction "Cathode_2") (pintype "passive"))
      (node (ref "U5") (pin "108") (pinfunction "VPP_2V5_108") (pintype "power_in"))
    )
    (net (code "33") (name "Net-(LED1-Anode)") (class "Default")
      (node (ref "LED1") (pin "1") (pinfunction "Anode_1") (pintype "passive"))
      (node (ref "R3") (pin "2") (pinfunction "2_2") (pintype "passive"))
    )
    (net (code "34") (name "Net-(LED2-Anode)") (class "Default")
      (node (ref "LED2") (pin "1") (pinfunction "Anode_1") (pintype "passive"))
      (node (ref "R21") (pin "2") (pinfunction "2_2") (pintype "passive"))
    )
    (net (code "35") (name "Net-(LED3-Anode)") (class "Default")
      (node (ref "LED3") (pin "1") (pinfunction "Anode_1") (pintype "passive"))
      (node (ref "R22") (pin "2") (pinfunction "2_2") (pintype "passive"))
    )
    (net (code "36") (name "Net-(LED4-Anode)") (class "Default")
      (node (ref "LED4") (pin "1") (pinfunction "Anode_1") (pintype "passive"))
      (node (ref "R23") (pin "2") (pinfunction "2_2") (pintype "passive"))
    )
    (net (code "37") (name "Net-(U1-Vin)") (class "Default")
      (node (ref "C4") (pin "1") (pinfunction "1_1") (pintype "passive"))
      (node (ref "R32") (pin "2") (pinfunction "2_2") (pintype "passive"))
      (node (ref "U1") (pin "3") (pinfunction "Vin_3") (pintype "passive"))
    )
    (net (code "38") (name "Net-(U2-ADJ)") (class "Default")
      (node (ref "C7") (pin "2") (pinfunction "2_2") (pintype "passive"))
      (node (ref "R1") (pin "1") (pinfunction "1_1") (pintype "passive"))
      (node (ref "R2") (pin "2") (pinfunction "2_2") (pintype "passive"))
      (node (ref "U2") (pin "4") (pinfunction "ADJ_4") (pintype "passive"))
    )
    (net (code "39") (name "Net-(U2-Enable)") (class "Default")
      (node (ref "C5") (pin "2") (pinfunction "2_2") (pintype "passive"))
      (node (ref "C6") (pin "2") (pinfunction "2_2") (pintype "passive"))
      (node (ref "R35") (pin "1") (pinfunction "1_1") (pintype "passive"))
      (node (ref "U2") (pin "1") (pinfunction "Vin_1") (pintype "passive"))
      (node (ref "U2") (pin "3") (pinfunction "Enable_3") (pintype "passive"))
    )
    (net (code "40") (name "Net-(U3-Vin)") (class "Default")
      (node (ref "C9") (pin "1") (pinfunction "1_1") (pintype "passive"))
      (node (ref "R33") (pin "2") (pinfunction "2_2") (pintype "passive"))
      (node (ref "U3") (pin "3") (pinfunction "Vin_3") (pintype "passive"))
    )
    (net (code "41") (name "Net-(U4-Vin)") (class "Default")
      (node (ref "C10") (pin "2") (pinfunction "2_2") (pintype "passive"))
      (node (ref "C8") (pin "2") (pinfunction "2_2") (pintype "passive"))
      (node (ref "R34") (pin "2") (pinfunction "2_2") (pintype "passive"))
      (node (ref "U4") (pin "3") (pinfunction "Vin_3") (pintype "power_in"))
    )
    (net (code "42") (name "Net-(U5C-IOB_103_CBSEL0)") (class "Default")
      (node (ref "TP8") (pin "1") (pinfunction "1_1") (pintype "passive"))
      (node (ref "U5") (pin "63") (pinfunction "IOB_103_CBSEL0_63") (pintype "bidirectional"))
    )
    (net (code "43") (name "Net-(U5C-IOB_104_CBSEL1)") (class "Default")
      (node (ref "TP9") (pin "1") (pinfunction "1_1") (pintype "passive"))
      (node (ref "U5") (pin "64") (pinfunction "IOB_104_CBSEL1_64") (pintype "bidirectional"))
    )
    (net (code "44") (name "Net-(U9-~{CS})") (class "Default")
      (node (ref "P3") (pin "2") (pinfunction "2_2") (pintype "passive"))
      (node (ref "R14") (pin "1") (pinfunction "1_1") (pintype "passive"))
      (node (ref "U9") (pin "1") (pinfunction "~{CS}_1") (pintype "passive"))
    )
    (net (code "45") (name "Net-(U9-~{HOLD})") (class "Default")
      (node (ref "R15") (pin "1") (pinfunction "1_1") (pintype "passive"))
      (node (ref "U9") (pin "7") (pinfunction "~{HOLD}_7") (pintype "passive"))
    )
    (net (code "46") (name "Net-(U9-~{WP})") (class "Default")
      (node (ref "R17") (pin "1") (pinfunction "1_1") (pintype "passive"))
      (node (ref "U9") (pin "3") (pinfunction "~{WP}_3") (pintype "passive"))
    )
    (net (code "47") (name "VCC_1V2") (class "Default")
      (node (ref "C1") (pin "1") (pinfunction "1_1") (pintype "passive"))
      (node (ref "C28") (pin "1") (pinfunction "1_1") (pintype "passive"))
      (node (ref "C31") (pin "1") (pinfunction "1_1") (pintype "passive"))
      (node (ref "C34") (pin "1") (pinfunction "1_1") (pintype "passive"))
      (node (ref "C36") (pin "1") (pinfunction "1_1") (pintype "passive"))
      (node (ref "C41") (pin "1") (pinfunction "1_1") (pintype "passive"))
      (node (ref "C42") (pin "1") (pinfunction "1_1") (pintype "passive"))
      (node (ref "TP1") (pin "1") (pinfunction "1_1") (pintype "passive"))
      (node (ref "U1") (pin "2") (pinfunction "Vout_2") (pintype "passive"))
      (node (ref "U5") (pin "111") (pinfunction "VCC_111") (pintype "power_in"))
      (node (ref "U5") (pin "126") (pinfunction "VCCPLL1_126") (pintype "power_in"))
      (node (ref "U5") (pin "27") (pinfunction "VCC_27") (pintype "power_in"))
      (node (ref "U5") (pin "40") (pinfunction "VCC_40") (pintype "power_in"))
      (node (ref "U5") (pin "54") (pinfunction "VCCPLL0_54") (pintype "power_in"))
      (node (ref "U5") (pin "92") (pinfunction "VCC_92") (pintype "power_in"))
    )
    (net (code "48") (name "VCC_3V3") (class "Default")
      (node (ref "C11") (pin "1") (pinfunction "1_1") (pintype "passive"))
      (node (ref "C21") (pin "2") (pinfunction "2_2") (pintype "passive"))
      (node (ref "C32") (pin "1") (pinfunction "1_1") (pintype "passive"))
      (node (ref "C37") (pin "1") (pinfunction "1_1") (pintype "passive"))
      (node (ref "C38") (pin "1") (pinfunction "1_1") (pintype "passive"))
      (node (ref "C39") (pin "1") (pinfunction "1_1") (pintype "passive"))
      (node (ref "C40") (pin "1") (pinfunction "1_1") (pintype "passive"))
      (node (ref "R14") (pin "2") (pinfunction "2_2") (pintype "passive"))
      (node (ref "R15") (pin "2") (pinfunction "2_2") (pintype "passive"))
      (node (ref "R17") (pin "2") (pinfunction "2_2") (pintype "passive"))
      (node (ref "R18") (pin "2") (pinfunction "2_2") (pintype "passive"))
      (node (ref "R26") (pin "1") (pinfunction "1_1") (pintype "passive"))
      (node (ref "R27") (pin "1") (pinfunction "1_1") (pintype "passive"))
      (node (ref "R3") (pin "1") (pinfunction "1_1") (pintype "passive"))
      (node (ref "TP3") (pin "1") (pinfunction "1_1") (pintype "passive"))
      (node (ref "U3") (pin "2") (pinfunction "Vout_2") (pintype "passive"))
      (node (ref "U5") (pin "30") (pinfunction "VCCIO_3_30") (pintype "power_in"))
      (node (ref "U5") (pin "46") (pinfunction "VCCIO_2_46") (pintype "power_in"))
      (node (ref "U5") (pin "57") (pinfunction "VCCIO_2_57") (pintype "power_in"))
      (node (ref "U5") (pin "6") (pinfunction "VCCIO_3_6") (pintype "power_in"))
      (node (ref "U5") (pin "72") (pinfunction "VCC_SPI_72") (pintype "power_in"))
      (node (ref "U9") (pin "8") (pinfunction "VCC_8") (pintype "passive"))
    )
    (net (code "49") (name "VCC_PWR") (class "Default")
      (node (ref "P1") (pin "1") (pinfunction "1_1") (pintype "passive"))
      (node (ref "R32") (pin "1") (pinfunction "1_1") (pintype "passive"))
      (node (ref "R33") (pin "1") (pinfunction "1_1") (pintype "passive"))
      (node (ref "R34") (pin "1") (pinfunction "1_1") (pintype "passive"))
      (node (ref "R35") (pin "2") (pinfunction "2_2") (pintype "passive"))
    )
    (net (code "50") (name "unconnected-(U5E-NC-Pad35)") (class "Default")
      (node (ref "U5") (pin "35") (pinfunction "NC_35") (pintype "passive+no_connect"))
    )
    (net (code "51") (name "unconnected-(U5E-NC-Pad36)") (class "Default")
      (node (ref "U5") (pin "36") (pinfunction "NC_36") (pintype "passive+no_connect"))
    )
    (net (code "52") (name "unconnected-(U5E-NC-Pad50)") (class "Default")
      (node (ref "U5") (pin "50") (pinfunction "NC_50") (pintype "passive+no_connect"))
    )
    (net (code "53") (name "unconnected-(U5E-NC-Pad51)") (class "Default")
      (node (ref "U5") (pin "51") (pinfunction "NC_51") (pintype "passive+no_connect"))
    )
    (net (code "54") (name "unconnected-(U5E-NC-Pad58)") (class "Default")
      (node (ref "U5") (pin "58") (pinfunction "NC_58") (pintype "passive+no_connect"))
    )
    (net (code "55") (name "unconnected-(U5E-NC-Pad77)") (class "Default")
      (node (ref "U5") (pin "77") (pinfunction "NC_77") (pintype "passive+no_connect"))
    )
    (net (code "56") (name "unconnected-(U5E-NC-Pad133)") (class "Default")
      (node (ref "U5") (pin "133") (pinfunction "NC_133") (pintype "passive+no_connect"))
    )
    (net (code "57") (name "unconnected-(U5E-VPP_FAST-Pad109)") (class "Default")
      (node (ref "U5") (pin "109") (pinfunction "VPP_FAST_109") (pintype "power_in+no_connect"))
    )
  )
)
